# reader.net
KiCad netlist of a schematic drawn in EAGLE
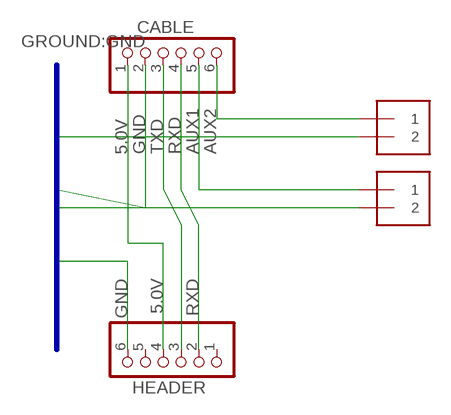
[diagram p0: schematic, sheet 1]

(export (version "E")
  (design (tool "Eeschema 10.0.6"))
  (components
    (comp (ref "AUX1")
      (value "1X2-3.5MM")
      (footprint "eagle-import:1X2-3.5MM")
      (libsource (lib "eagle-import") (part "1X2-3.5MM"))
    )
    (comp (ref "AUX2")
      (value "1X2-3.5MM")
      (footprint "eagle-import:1X2-3.5MM")
      (libsource (lib "eagle-import") (part "1X2-3.5MM"))
    )
    (comp (ref "CABLE")
      (value "PINHD-1X6")
      (footprint "eagle-import:1X06")
      (libsource (lib "eagle-import") (part "PINHD-1X6"))
    )
    (comp (ref "HEADER")
      (value "PINHD-1X6")
      (footprint "eagle-import:1X06")
      (libsource (lib "eagle-import") (part "PINHD-1X6"))
    )
  )
  (nets
    (net (code "2") (name "/5.0V") (class "Default")
      (node (ref "CABLE") (pin "1") (pinfunction "1_1") (pintype "passive"))
      (node (ref "HEADER") (pin "4") (pinfunction "4_4") (pintype "passive"))
    )
    (net (code "3") (name "/AUX1") (class "Default")
      (node (ref "AUX1") (pin "1") (pinfunction "1_1") (pintype "passive"))
      (node (ref "CABLE") (pin "5") (pinfunction "5_5") (pintype "passive"))
    )
    (net (code "4") (name "/AUX2") (class "Default")
      (node (ref "AUX2") (pin "1") (pinfunction "1_1") (pintype "passive"))
      (node (ref "CABLE") (pin "6") (pinfunction "6_6") (pintype "passive"))
    )
    (net (code "5") (name "/GND") (class "Default")
      (node (ref "AUX1") (pin "2") (pinfunction "2_2") (pintype "passive"))
      (node (ref "AUX2") (pin "2") (pinfunction "2_2") (pintype "passive"))
      (node (ref "CABLE") (pin "2") (pinfunction "2_2") (pintype "passive"))
      (node (ref "HEADER") (pin "6") (pinfunction "6_6") (pintype "passive"))
    )
    (net (code "6") (name "/RXD") (class "Default")
      (node (ref "CABLE") (pin "4") (pinfunction "4_4") (pintype "passive"))
      (node (ref "HEADER") (pin "2") (pinfunction "2_2") (pintype "passive"))
    )
    (net (code "7") (name "/TXD") (class "Default")
      (node (ref "CABLE") (pin "3") (pinfunction "3_3") (pintype "passive"))
      (node (ref "HEADER") (pin "3") (pinfunction "3_3") (pintype "passive"))
    )
    (net (code "9") (name "unconnected-(HEADER-Pad1)") (class "Default")
      (node (ref "HEADER") (pin "1") (pinfunction "1_1") (pintype "passive"))
    )
    (net (code "10") (name "unconnected-(HEADER-Pad5)") (class "Default")
      (node (ref "HEADER") (pin "5") (pinfunction "5_5") (pintype "passive"))
    )
  )
)
